# leo_MOTORS.net
KiCad netlist of a schematic drawn in Altium Designer
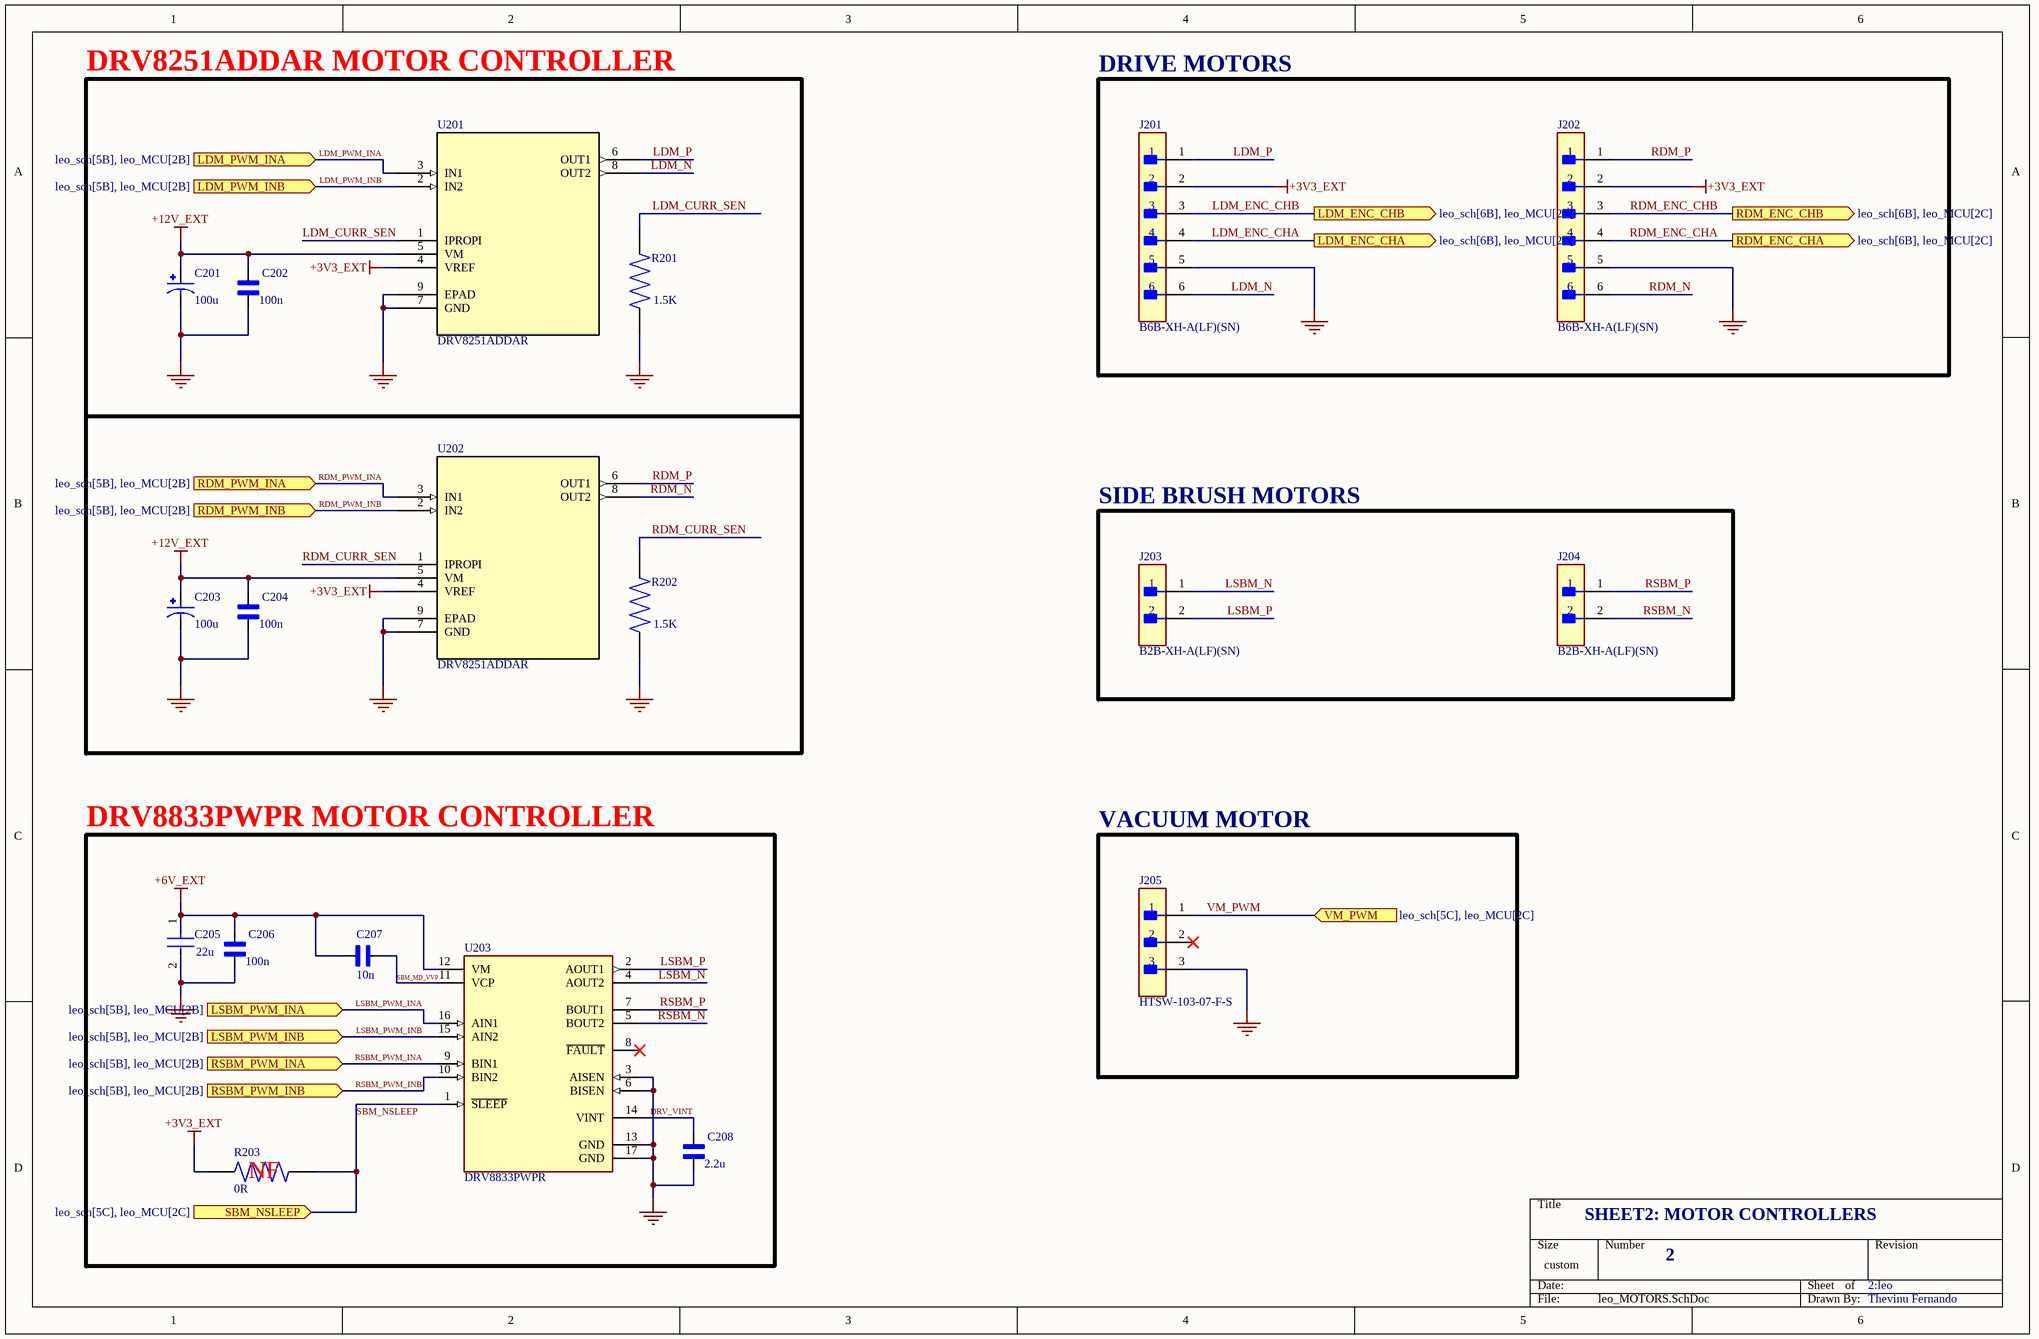
[diagram p0: leo_MOTORS.SchDoc]

(export (version "E")
  (design (tool "Eeschema 10.0.6"))
  (components
    (comp (ref "C201")
      (value "100u")
      (footprint "CAP_EEHZA1E101XP")
      (description "100F 25V Aluminum - Polymer Capacitors Radial, Can - SMD 30mOhm 10000 Hrs @ 105C")
      (fields (field (name "MF") "Panasonic") (field (name "MP") "EEHZA1E101XP"))
      (libsource (lib "leo_schlib") (part "EEHZA1E101XP"))
    )
    (comp (ref "C202")
      (value "100n")
      (footprint "CAP_0603")
      (description "Ceramic Capacitor X5R 0603 (1608 Metric)")
      (fields (field (name "MF") "Samsung Electro-Mechanics") (field (name "MP") "CL10A475KO8NNNC"))
      (libsource (lib "leo_schlib") (part "CAP_0603"))
    )
    (comp (ref "C203")
      (value "100u")
      (footprint "CAP_EEHZA1E101XP")
      (description "100F 25V Aluminum - Polymer Capacitors Radial, Can - SMD 30mOhm 10000 Hrs @ 105C")
      (fields (field (name "MF") "Panasonic") (field (name "MP") "EEHZA1E101XP"))
      (libsource (lib "leo_schlib") (part "EEHZA1E101XP"))
    )
    (comp (ref "C204")
      (value "100n")
      (footprint "CAP_0603")
      (description "Ceramic Capacitor X5R 0603 (1608 Metric)")
      (fields (field (name "MF") "Samsung Electro-Mechanics") (field (name "MP") "CL10A475KO8NNNC"))
      (libsource (lib "leo_schlib") (part "CAP_0603"))
    )
    (comp (ref "C205")
      (value "22u")
      (footprint "CAP_1206")
      (fields
        (field (name "MOUSER PART NUMBER") "187-CL31A226KAHNNNE")
        (field (name "PART NUMBER") "CL31A226KAHNNNE")
        (field (name "DIGIKEY PART NUMBER") "1276-3047-1-ND")
      )
      (libsource (lib "leo_schlib") (part "CAP_1206"))
    )
    (comp (ref "C206")
      (value "100n")
      (footprint "CAP_0402")
      (description "Ceramic Capacitor X7R 0402 (1005 Metric)")
      (fields (field (name "MF") "Samsung") (field (name "MP") "CL05B104KO5NNNC"))
      (libsource (lib "leo_schlib") (part "CAP_0402"))
    )
    (comp (ref "C207")
      (value "10n")
      (footprint "CAP_0402")
      (description "Ceramic Capacitor X7R 0402 (1005 Metric)")
      (fields (field (name "MF") "Samsung") (field (name "MP") "CL05B104KO5NNNC"))
      (libsource (lib "") (part "CAP_0402_1"))
    )
    (comp (ref "C208")
      (value "2.2u")
      (footprint "CAP_0603")
      (description "Ceramic Capacitor X5R 0603 (1608 Metric)")
      (fields (field (name "MF") "Samsung Electro-Mechanics") (field (name "MP") "CL10A475KO8NNNC"))
      (libsource (lib "leo_schlib") (part "CAP_0603"))
    )
    (comp (ref "J201")
      (value "B6B-XH-A(LF)(SN)")
      (footprint "FP-B6B-XH-A_LF_SN-MFG")
      (description "CONN HEADER VERT 6POS 2.5MM")
      (libsource (lib "leo_schlib") (part "B6B-XH-A(LF)(SN)"))
    )
    (comp (ref "J202")
      (value "B6B-XH-A(LF)(SN)")
      (footprint "FP-B6B-XH-A_LF_SN-MFG")
      (description "CONN HEADER VERT 6POS 2.5MM")
      (libsource (lib "leo_schlib") (part "B6B-XH-A(LF)(SN)"))
    )
    (comp (ref "J203")
      (value "B2B-XH-A(LF)(SN)")
      (footprint "FP-B2B-XH-A_LF_SN-MFG")
      (description "CONN HEADER VERT 2POS 2.5MM")
      (libsource (lib "leo_schlib") (part "B2B-XH-A(LF)(SN)"))
    )
    (comp (ref "J204")
      (value "B2B-XH-A(LF)(SN)")
      (footprint "FP-B2B-XH-A_LF_SN-MFG")
      (description "CONN HEADER VERT 2POS 2.5MM")
      (libsource (lib "leo_schlib") (part "B2B-XH-A(LF)(SN)"))
    )
    (comp (ref "J205")
      (value "HTSW-103-07-F-S")
      (footprint "FP-HTSW-103-07-F-S-MFG")
      (description "CONN HEADER VERT 3POS 2.54MM")
      (libsource (lib "leo_schlib") (part "3P_MHEADER"))
    )
    (comp (ref "R201")
      (value "1.5K")
      (footprint "RES_0603")
      (description "0603 Thin Film Resistor AEC-Q200")
      (fields (field (name "MP") "ERA3VEB1501V"))
      (libsource (lib "leo_schlib") (part "RES_0603"))
    )
    (comp (ref "R202")
      (value "1.5K")
      (footprint "RES_0603")
      (description "0603 Thin Film Resistor AEC-Q200")
      (fields (field (name "MP") "ERA3VEB1501V"))
      (libsource (lib "leo_schlib") (part "RES_0603"))
    )
    (comp (ref "R203")
      (value "0R")
      (footprint "RES_0402")
      (description "Chip Resistor 0402 (1005 Metric) Automotive AEC-Q200 Thick Film")
      (fields (field (name "MF") "Panasonic") (field (name "MP") "ERJ-2RKF1002X"))
      (libsource (lib "leo_schlib") (part "RES_0402"))
    )
    (comp (ref "U201")
      (value "DRV8251ADDAR")
      (footprint "SOIC8_DDA_TEX")
      (fields (field (name "COPYRIGHT") "Copyright (C) 2026 Ultra Librarian. All rights reserved."))
      (libsource (lib "leo_schlib") (part "DRV8251ADDAR"))
    )
    (comp (ref "U202")
      (value "DRV8251ADDAR")
      (footprint "SOIC8_DDA_TEX")
      (fields (field (name "COPYRIGHT") "Copyright (C) 2026 Ultra Librarian. All rights reserved."))
      (libsource (lib "leo_schlib") (part "DRV8251ADDAR"))
    )
    (comp (ref "U203")
      (value "DRV8833PWPR")
      (footprint "FP-PWP0016C-IPC_B")
      (description "IC MOTOR DRIVER PAR 16HTSSOP")
      (libsource (lib "leo_schlib") (part "DRV8833PWPR"))
    )
  )
  (nets
    (net (code "1") (name "+3V3_EXT") (class "Default")
      (node (ref "J201") (pin "2") (pinfunction "2_2") (pintype "passive"))
      (node (ref "J202") (pin "2") (pinfunction "2_2") (pintype "passive"))
      (node (ref "R203") (pin "2") (pinfunction "2_2") (pintype "passive"))
      (node (ref "U201") (pin "4") (pinfunction "VREF_4") (pintype "power_in"))
      (node (ref "U202") (pin "4") (pinfunction "VREF_4") (pintype "power_in"))
    )
    (net (code "2") (name "+6V_EXT") (class "Default")
      (node (ref "C205") (pin "1") (pinfunction "1_1") (pintype "passive"))
      (node (ref "C206") (pin "2") (pinfunction "2_2") (pintype "passive"))
      (node (ref "C207") (pin "2") (pinfunction "2_2") (pintype "passive"))
      (node (ref "U203") (pin "12") (pinfunction "VM_12") (pintype "power_in"))
    )
    (net (code "3") (name "+12V_EXT") (class "Default")
      (node (ref "C201") (pin "1") (pinfunction "1_1") (pintype "passive"))
      (node (ref "C202") (pin "2") (pinfunction "2_2") (pintype "passive"))
      (node (ref "C203") (pin "1") (pinfunction "1_1") (pintype "passive"))
      (node (ref "C204") (pin "2") (pinfunction "2_2") (pintype "passive"))
      (node (ref "U201") (pin "5") (pinfunction "VM_5") (pintype "power_in"))
      (node (ref "U202") (pin "5") (pinfunction "VM_5") (pintype "power_in"))
    )
    (net (code "4") (name "/DRV_VINT") (class "Default")
      (node (ref "C208") (pin "2") (pinfunction "2_2") (pintype "passive"))
      (node (ref "U203") (pin "14") (pinfunction "VINT_14") (pintype "power_in"))
    )
    (net (code "5") (name "/LDM_CURR_SEN") (class "Default")
      (node (ref "R201") (pin "2") (pinfunction "2_2") (pintype "passive"))
      (node (ref "U201") (pin "1") (pinfunction "IPROPI_1") (pintype "power_in"))
    )
    (net (code "6") (name "/LDM_ENC_CHA") (class "Default")
      (node (ref "J201") (pin "4") (pinfunction "4_4") (pintype "passive"))
    )
    (net (code "7") (name "/LDM_ENC_CHB") (class "Default")
      (node (ref "J201") (pin "3") (pinfunction "3_3") (pintype "passive"))
    )
    (net (code "8") (name "/LDM_N") (class "Default")
      (node (ref "J201") (pin "6") (pinfunction "6_6") (pintype "passive"))
      (node (ref "U201") (pin "8") (pinfunction "OUT2_8") (pintype "output"))
    )
    (net (code "9") (name "/LDM_P") (class "Default")
      (node (ref "J201") (pin "1") (pinfunction "1_1") (pintype "passive"))
      (node (ref "U201") (pin "6") (pinfunction "OUT1_6") (pintype "output"))
    )
    (net (code "10") (name "/LDM_PWM_INA") (class "Default")
      (node (ref "U201") (pin "3") (pinfunction "IN1_3") (pintype "input"))
    )
    (net (code "11") (name "/LDM_PWM_INB") (class "Default")
      (node (ref "U201") (pin "2") (pinfunction "IN2_2") (pintype "input"))
    )
    (net (code "12") (name "/LSBM_N") (class "Default")
      (node (ref "J203") (pin "1") (pinfunction "1_1") (pintype "passive"))
      (node (ref "U203") (pin "4") (pinfunction "AOUT2_4") (pintype "tri_state"))
    )
    (net (code "13") (name "/LSBM_P") (class "Default")
      (node (ref "J203") (pin "2") (pinfunction "2_2") (pintype "passive"))
      (node (ref "U203") (pin "2") (pinfunction "AOUT1_2") (pintype "output"))
    )
    (net (code "14") (name "/LSBM_PWM_INA") (class "Default")
      (node (ref "U203") (pin "16") (pinfunction "AIN1_16") (pintype "input"))
    )
    (net (code "15") (name "/LSBM_PWM_INB") (class "Default")
      (node (ref "U203") (pin "15") (pinfunction "AIN2_15") (pintype "input"))
    )
    (net (code "16") (name "/RDM_CURR_SEN") (class "Default")
      (node (ref "R202") (pin "2") (pinfunction "2_2") (pintype "passive"))
      (node (ref "U202") (pin "1") (pinfunction "IPROPI_1") (pintype "power_in"))
    )
    (net (code "17") (name "/RDM_ENC_CHA") (class "Default")
      (node (ref "J202") (pin "4") (pinfunction "4_4") (pintype "passive"))
    )
    (net (code "18") (name "/RDM_ENC_CHB") (class "Default")
      (node (ref "J202") (pin "3") (pinfunction "3_3") (pintype "passive"))
    )
    (net (code "19") (name "/RDM_N") (class "Default")
      (node (ref "J202") (pin "6") (pinfunction "6_6") (pintype "passive"))
      (node (ref "U202") (pin "8") (pinfunction "OUT2_8") (pintype "output"))
    )
    (net (code "20") (name "/RDM_P") (class "Default")
      (node (ref "J202") (pin "1") (pinfunction "1_1") (pintype "passive"))
      (node (ref "U202") (pin "6") (pinfunction "OUT1_6") (pintype "output"))
    )
    (net (code "21") (name "/RDM_PWM_INA") (class "Default")
      (node (ref "U202") (pin "3") (pinfunction "IN1_3") (pintype "input"))
    )
    (net (code "22") (name "/RDM_PWM_INB") (class "Default")
      (node (ref "U202") (pin "2") (pinfunction "IN2_2") (pintype "input"))
    )
    (net (code "23") (name "/RSBM_N") (class "Default")
      (node (ref "J204") (pin "2") (pinfunction "2_2") (pintype "passive"))
      (node (ref "U203") (pin "5") (pinfunction "BOUT2_5") (pintype "tri_state"))
    )
    (net (code "24") (name "/RSBM_P") (class "Default")
      (node (ref "J204") (pin "1") (pinfunction "1_1") (pintype "passive"))
      (node (ref "U203") (pin "7") (pinfunction "BOUT1_7") (pintype "tri_state"))
    )
    (net (code "25") (name "/RSBM_PWM_INA") (class "Default")
      (node (ref "U203") (pin "9") (pinfunction "BIN1_9") (pintype "input"))
    )
    (net (code "26") (name "/RSBM_PWM_INB") (class "Default")
      (node (ref "U203") (pin "10") (pinfunction "BIN2_10") (pintype "input"))
    )
    (net (code "27") (name "/SBM_MD_VVP") (class "Default")
      (node (ref "C207") (pin "1") (pinfunction "1_1") (pintype "passive"))
      (node (ref "U203") (pin "11") (pinfunction "VCP_11") (pintype "passive"))
    )
    (net (code "28") (name "/SBM_NSLEEP") (class "Default")
      (node (ref "R203") (pin "1") (pinfunction "1_1") (pintype "passive"))
      (node (ref "U203") (pin "1") (pinfunction "~{SLEEP}_1") (pintype "input"))
    )
    (net (code "29") (name "/VM_PWM") (class "Default")
      (node (ref "J205") (pin "1") (pinfunction "1_1") (pintype "passive"))
    )
    (net (code "30") (name "GND") (class "Default")
      (node (ref "C201") (pin "2") (pinfunction "2_2") (pintype "passive"))
      (node (ref "C202") (pin "1") (pinfunction "1_1") (pintype "passive"))
      (node (ref "C203") (pin "2") (pinfunction "2_2") (pintype "passive"))
      (node (ref "C204") (pin "1") (pinfunction "1_1") (pintype "passive"))
      (node (ref "C205") (pin "2") (pinfunction "2_2") (pintype "passive"))
      (node (ref "C206") (pin "1") (pinfunction "1_1") (pintype "passive"))
      (node (ref "C208") (pin "1") (pinfunction "1_1") (pintype "passive"))
      (node (ref "J201") (pin "5") (pinfunction "5_5") (pintype "passive"))
      (node (ref "J202") (pin "5") (pinfunction "5_5") (pintype "passive"))
      (node (ref "J205") (pin "3") (pinfunction "3_3") (pintype "passive"))
      (node (ref "R201") (pin "1") (pinfunction "1_1") (pintype "passive"))
      (node (ref "R202") (pin "1") (pinfunction "1_1") (pintype "passive"))
      (node (ref "U201") (pin "7") (pinfunction "GND_7") (pintype "power_in"))
      (node (ref "U201") (pin "9") (pinfunction "EPAD_9") (pintype "power_in"))
      (node (ref "U202") (pin "7") (pinfunction "GND_7") (pintype "power_in"))
      (node (ref "U202") (pin "9") (pinfunction "EPAD_9") (pintype "power_in"))
      (node (ref "U203") (pin "13") (pinfunction "GND_13") (pintype "power_in"))
      (node (ref "U203") (pin "17") (pinfunction "GND_17") (pintype "power_in"))
      (node (ref "U203") (pin "3") (pinfunction "AISEN_3") (pintype "input"))
      (node (ref "U203") (pin "6") (pinfunction "BISEN_6") (pintype "input"))
    )
    (net (code "31") (name "unconnected-(J205-Pad2)") (class "Default")
      (node (ref "J205") (pin "2") (pinfunction "2_2") (pintype "passive+no_connect"))
    )
    (net (code "32") (name "unconnected-(U203-~{FAULT}-Pad8)") (class "Default")
      (node (ref "U203") (pin "8") (pinfunction "~{FAULT}_8") (pintype "open_collector+no_connect"))
    )
  )
)
